# design.net
KiCad netlist of a schematic drawn in Altium Designer
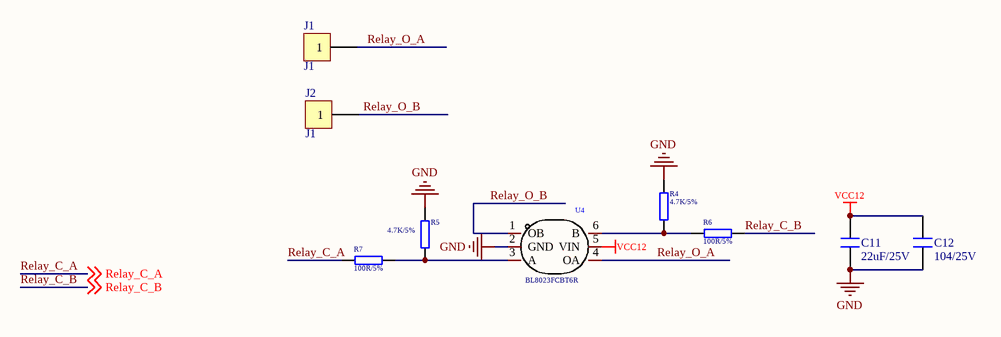
[diagram p0: 继电器.SchDoc]

(export (version "E")
  (design (tool "Eeschema 10.0.6"))
  (components
    (comp (ref "C11") (value "22uF/25V") (footprint "0603R") (libsource (lib "ES_Schematic") (part "CAP_1")))
    (comp (ref "C12") (value "104/25V") (footprint "0603R") (libsource (lib "ES_Schematic") (part "CAP_1")))
    (comp (ref "J1") (value "J1") (footprint "贴片焊盘V1（3*2椭圆）") (libsource (lib "ES_Schematic") (part "J1")))
    (comp (ref "J2") (value "J1") (footprint "贴片焊盘V1（3*2椭圆）") (libsource (lib "ES_Schematic") (part "J1")))
    (comp (ref "R4") (value "4.7K/5%") (footprint "0603R") (libsource (lib "ES_Schematic") (part "RES")))
    (comp (ref "R5") (value "4.7K/5%") (footprint "0603R") (libsource (lib "ES_Schematic") (part "RES")))
    (comp (ref "R6") (value "100R/5%") (footprint "0603R") (libsource (lib "ES_Schematic") (part "RES")))
    (comp (ref "R7") (value "100R/5%") (footprint "0603R") (libsource (lib "ES_Schematic") (part "RES")))
    (comp (ref "U4")
      (value "BL8023FCBT6R")
      (footprint "SOT-23-6")
      (fields (field (name "MANUFACTURER") "BL(上海贝岭)") (field (name "MANUFACTURER PART") "BL8023HCB6TR"))
      (libsource (lib "altium-import") (part "root_0_BL8023HCB6TR_"))
    )
  )
  (nets
    (net (code "1") (name "/Relay_O_A") (class "Default")
      (node (ref "J1") (pin "1") (pinfunction "1_1") (pintype "passive"))
      (node (ref "U4") (pin "4") (pinfunction "OA_4") (pintype "passive"))
    )
    (net (code "2") (name "/Relay_O_B") (class "Default")
      (node (ref "J2") (pin "1") (pinfunction "1_1") (pintype "passive"))
      (node (ref "U4") (pin "1") (pinfunction "OB_1") (pintype "passive"))
    )
    (net (code "3") (name "GND") (class "Default")
      (node (ref "C11") (pin "1") (pinfunction "1_1") (pintype "passive"))
      (node (ref "C12") (pin "1") (pinfunction "1_1") (pintype "passive"))
      (node (ref "R4") (pin "1") (pinfunction "1_1") (pintype "passive"))
      (node (ref "R5") (pin "1") (pinfunction "1_1") (pintype "passive"))
      (node (ref "U4") (pin "2") (pinfunction "GND_2") (pintype "passive"))
    )
    (net (code "4") (name "Net-(U4-A)") (class "Default")
      (node (ref "R5") (pin "2") (pinfunction "2_2") (pintype "passive"))
      (node (ref "R7") (pin "1") (pinfunction "1_1") (pintype "passive"))
      (node (ref "U4") (pin "3") (pinfunction "A_3") (pintype "passive"))
    )
    (net (code "5") (name "Net-(U4-B)") (class "Default")
      (node (ref "R4") (pin "2") (pinfunction "2_2") (pintype "passive"))
      (node (ref "R6") (pin "2") (pinfunction "2_2") (pintype "passive"))
      (node (ref "U4") (pin "6") (pinfunction "B_6") (pintype "passive"))
    )
    (net (code "6") (name "Relay_C_A") (class "Default")
      (node (ref "R7") (pin "2") (pinfunction "2_2") (pintype "passive"))
    )
    (net (code "7") (name "Relay_C_B") (class "Default")
      (node (ref "R6") (pin "1") (pinfunction "1_1") (pintype "passive"))
    )
    (net (code "8") (name "VCC12") (class "Default")
      (node (ref "C11") (pin "2") (pinfunction "2_2") (pintype "passive"))
      (node (ref "C12") (pin "2") (pinfunction "2_2") (pintype "passive"))
      (node (ref "U4") (pin "5") (pinfunction "VIN_5") (pintype "passive"))
    )
  )
)
